# TestProject.net
KiCad netlist of a schematic drawn in Altium Designer
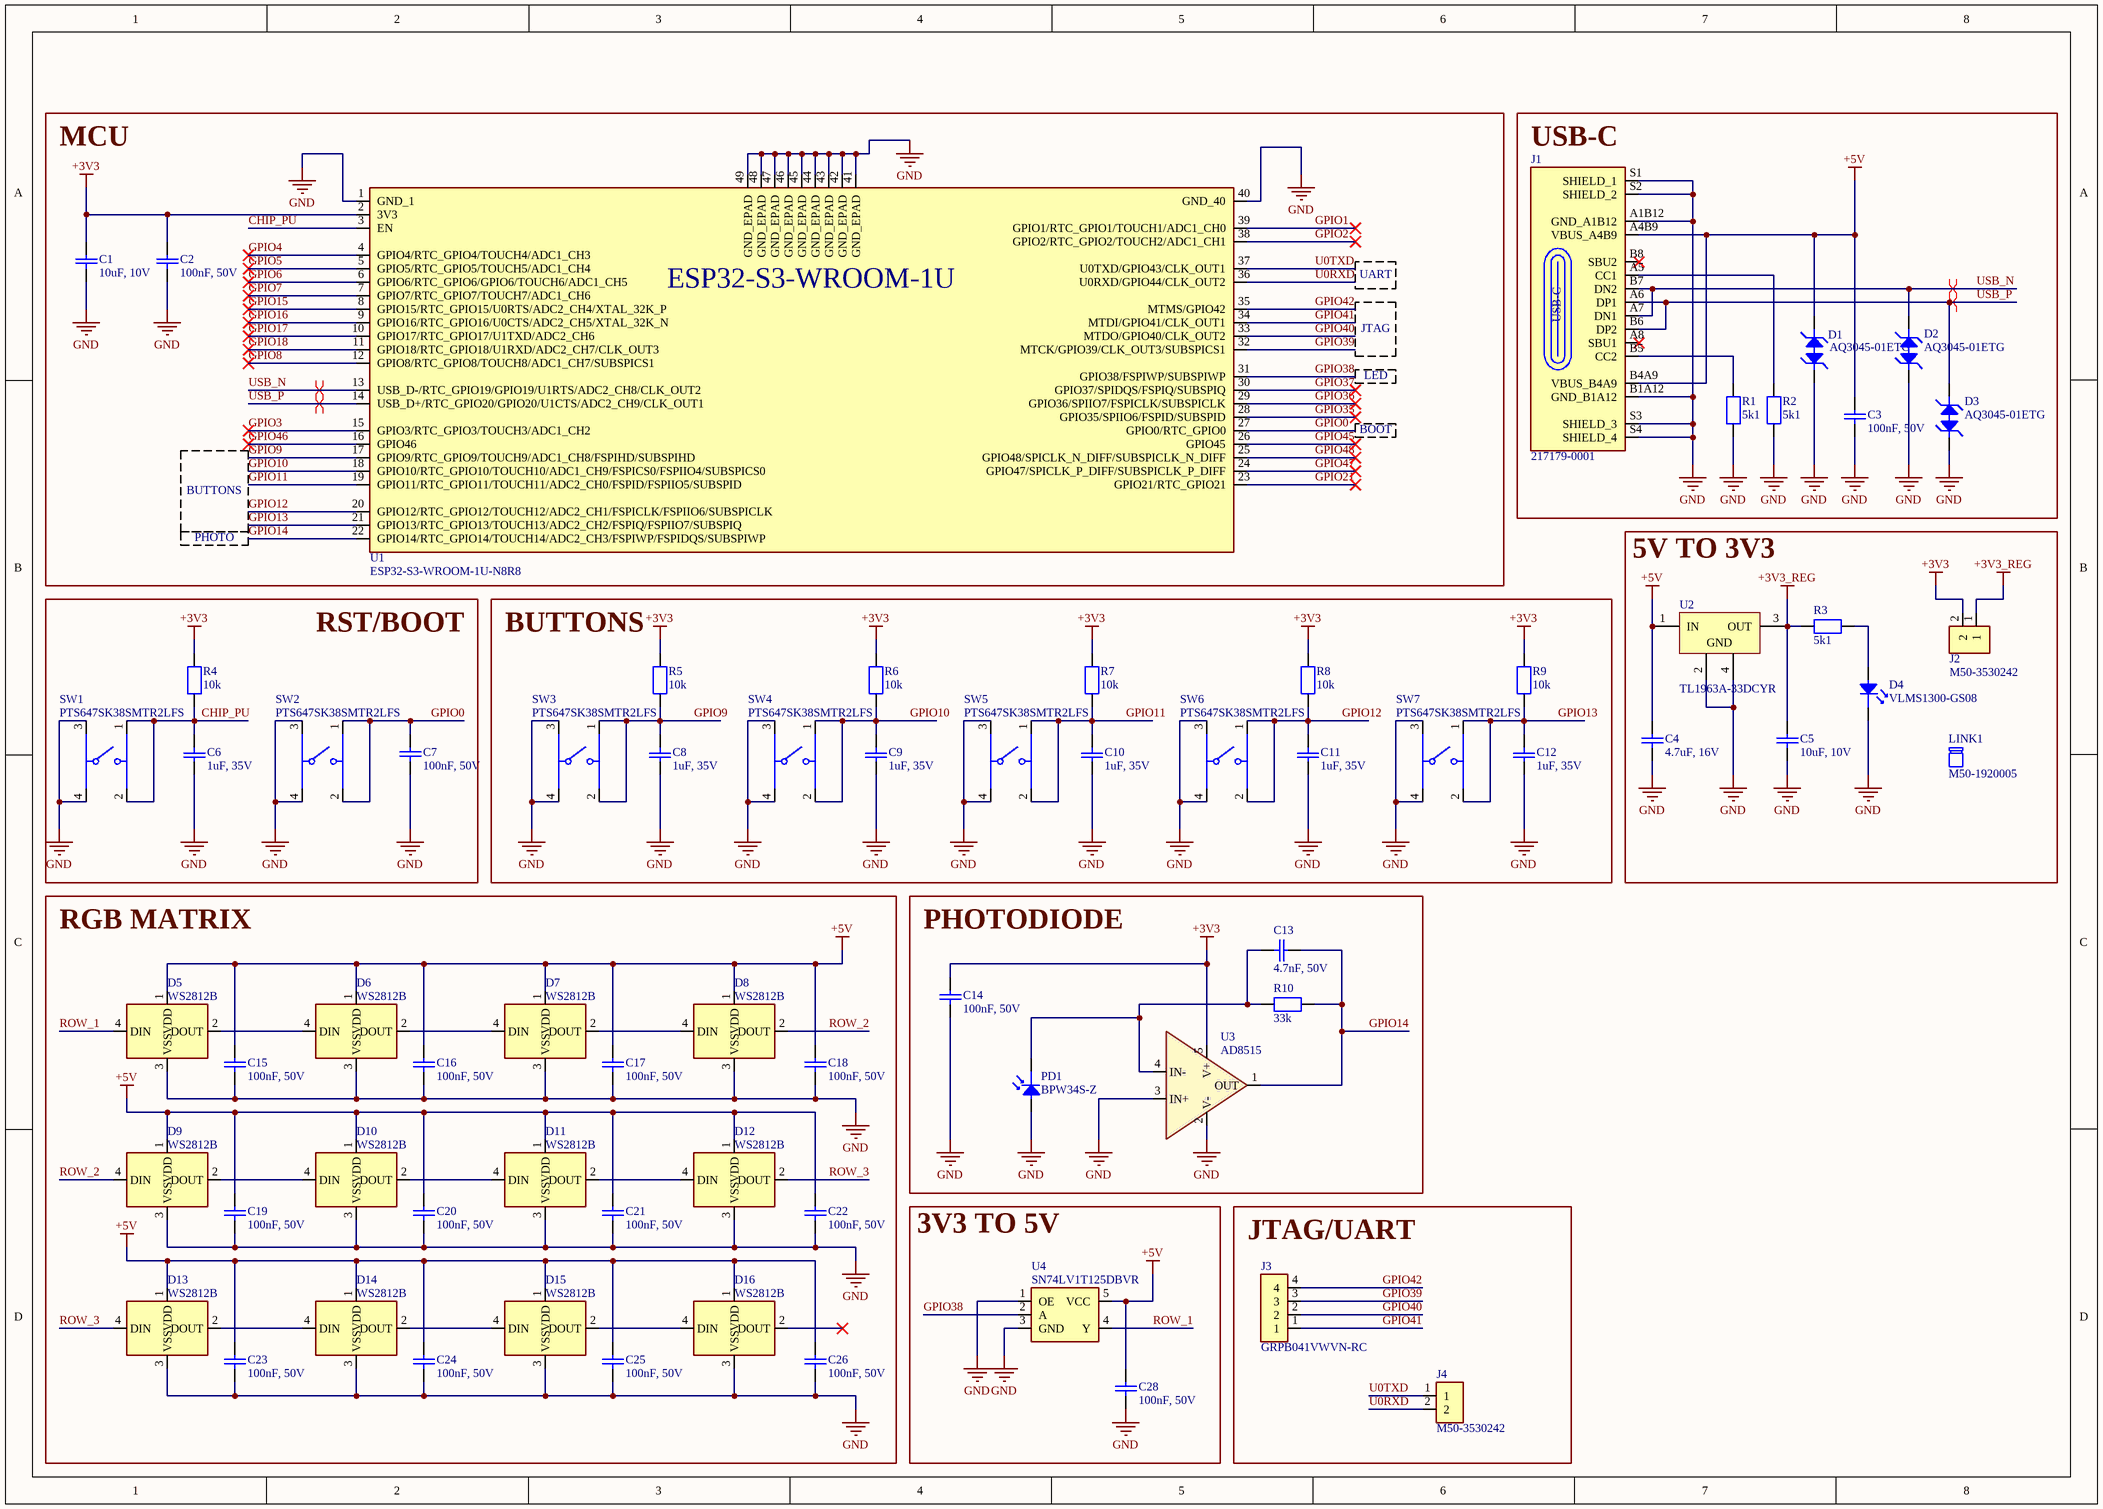
[diagram p0: TestProject.SchDoc]

(export (version "E")
  (design (tool "Eeschema 10.0.6"))
  (components
    (comp (ref "C1")
      (value "10uF, 10V")
      (footprint "CAPC1005X70N")
      (description "CAP CER 10UF 10V X5R 0402")
      (fields
        (field (name "MANUFACTURER") "Samsung")
        (field (name "MANUFACTURER PART NUMBER") "CL05A106MP5NRNC")
      )
      (libsource (lib "Schlib") (part "CL05A106MP5NRNC"))
    )
    (comp (ref "C2")
      (value "100nF, 50V")
      (footprint "CAPC1005X70N")
      (description "CAP CER 0.1UF 50V X7R 0402")
      (fields
        (field (name "MANUFACTURER") "Samsung")
        (field (name "MANUFACTURER PART NUMBER") "CL05B104KB5NNNC")
      )
      (libsource (lib "Schlib") (part "CL05B104KB5NNNC"))
    )
    (comp (ref "C3")
      (value "100nF, 50V")
      (footprint "CAPC1005X70N")
      (description "CAP CER 0.1UF 50V X7R 0402")
      (fields
        (field (name "MANUFACTURER") "Samsung")
        (field (name "MANUFACTURER PART NUMBER") "CL05B104KB5NNNC")
      )
      (libsource (lib "Schlib") (part "CL05B104KB5NNNC"))
    )
    (comp (ref "C4")
      (value "4.7uF, 16V")
      (footprint "CAPC1005X70N")
      (description "CAP CER 4.7UF 16V X5R 0402")
      (fields
        (field (name "MANUFACTURER") "Samsung")
        (field (name "MANUFACTURER PART NUMBER") "CL05A475MO5NUNC")
      )
      (libsource (lib "Schlib") (part "CL05A475MO5NUNC"))
    )
    (comp (ref "C5")
      (value "10uF, 10V")
      (footprint "CAPC1005X70N")
      (description "CAP CER 10UF 10V X5R 0402")
      (fields
        (field (name "MANUFACTURER") "Samsung")
        (field (name "MANUFACTURER PART NUMBER") "CL05A106MP5NRNC")
      )
      (libsource (lib "Schlib") (part "CL05A106MP5NRNC"))
    )
    (comp (ref "C6")
      (value "1uF, 35V")
      (footprint "CAPC1005X70N")
      (description "CAP CER 1UF 35V X5R 0402")
      (fields
        (field (name "MANUFACTURER") "Samsung")
        (field (name "MANUFACTURER PART NUMBER") "CL05A105KL5NRNC")
      )
      (libsource (lib "Schlib") (part "CL05A105KL5NRNC"))
    )
    (comp (ref "C7")
      (value "100nF, 50V")
      (footprint "CAPC1005X70N")
      (description "CAP CER 0.1UF 50V X7R 0402")
      (fields
        (field (name "MANUFACTURER") "Samsung")
        (field (name "MANUFACTURER PART NUMBER") "CL05B104KB5NNNC")
      )
      (libsource (lib "Schlib") (part "CL05B104KB5NNNC"))
    )
    (comp (ref "C8")
      (value "1uF, 35V")
      (footprint "CAPC1005X70N")
      (description "CAP CER 1UF 35V X5R 0402")
      (fields
        (field (name "MANUFACTURER") "Samsung")
        (field (name "MANUFACTURER PART NUMBER") "CL05A105KL5NRNC")
      )
      (libsource (lib "Schlib") (part "CL05A105KL5NRNC"))
    )
    (comp (ref "C9")
      (value "1uF, 35V")
      (footprint "CAPC1005X70N")
      (description "CAP CER 1UF 35V X5R 0402")
      (fields
        (field (name "MANUFACTURER") "Samsung")
        (field (name "MANUFACTURER PART NUMBER") "CL05A105KL5NRNC")
      )
      (libsource (lib "Schlib") (part "CL05A105KL5NRNC"))
    )
    (comp (ref "C10")
      (value "1uF, 35V")
      (footprint "CAPC1005X70N")
      (description "CAP CER 1UF 35V X5R 0402")
      (fields
        (field (name "MANUFACTURER") "Samsung")
        (field (name "MANUFACTURER PART NUMBER") "CL05A105KL5NRNC")
      )
      (libsource (lib "Schlib") (part "CL05A105KL5NRNC"))
    )
    (comp (ref "C11")
      (value "1uF, 35V")
      (footprint "CAPC1005X70N")
      (description "CAP CER 1UF 35V X5R 0402")
      (fields
        (field (name "MANUFACTURER") "Samsung")
        (field (name "MANUFACTURER PART NUMBER") "CL05A105KL5NRNC")
      )
      (libsource (lib "Schlib") (part "CL05A105KL5NRNC"))
    )
    (comp (ref "C12")
      (value "1uF, 35V")
      (footprint "CAPC1005X70N")
      (description "CAP CER 1UF 35V X5R 0402")
      (fields
        (field (name "MANUFACTURER") "Samsung")
        (field (name "MANUFACTURER PART NUMBER") "CL05A105KL5NRNC")
      )
      (libsource (lib "Schlib") (part "CL05A105KL5NRNC"))
    )
    (comp (ref "C13")
      (value "4.7nF, 50V")
      (footprint "CAPC1005X70N")
      (description "CAP CER 4700PF 50V X7R 0402")
      (fields
        (field (name "MANUFACTURER") "Samsung")
        (field (name "MANUFACTURER PART NUMBER") "CL05B472KB5VPNC")
      )
      (libsource (lib "Schlib") (part "CL05B472KB5VPNC"))
    )
    (comp (ref "C14")
      (value "100nF, 50V")
      (footprint "CAPC1005X70N")
      (description "CAP CER 0.1UF 50V X7R 0402")
      (fields
        (field (name "MANUFACTURER") "Samsung")
        (field (name "MANUFACTURER PART NUMBER") "CL05B104KB5NNNC")
      )
      (libsource (lib "Schlib") (part "CL05B104KB5NNNC"))
    )
    (comp (ref "C15")
      (value "100nF, 50V")
      (footprint "CAPC1005X70N")
      (description "CAP CER 0.1UF 50V X7R 0402")
      (fields
        (field (name "MANUFACTURER") "Samsung")
        (field (name "MANUFACTURER PART NUMBER") "CL05B104KB5NNNC")
      )
      (libsource (lib "Schlib") (part "CL05B104KB5NNNC"))
    )
    (comp (ref "C16")
      (value "100nF, 50V")
      (footprint "CAPC1005X70N")
      (description "CAP CER 0.1UF 50V X7R 0402")
      (fields
        (field (name "MANUFACTURER") "Samsung")
        (field (name "MANUFACTURER PART NUMBER") "CL05B104KB5NNNC")
      )
      (libsource (lib "Schlib") (part "CL05B104KB5NNNC"))
    )
    (comp (ref "C17")
      (value "100nF, 50V")
      (footprint "CAPC1005X70N")
      (description "CAP CER 0.1UF 50V X7R 0402")
      (fields
        (field (name "MANUFACTURER") "Samsung")
        (field (name "MANUFACTURER PART NUMBER") "CL05B104KB5NNNC")
      )
      (libsource (lib "Schlib") (part "CL05B104KB5NNNC"))
    )
    (comp (ref "C18")
      (value "100nF, 50V")
      (footprint "CAPC1005X70N")
      (description "CAP CER 0.1UF 50V X7R 0402")
      (fields
        (field (name "MANUFACTURER") "Samsung")
        (field (name "MANUFACTURER PART NUMBER") "CL05B104KB5NNNC")
      )
      (libsource (lib "Schlib") (part "CL05B104KB5NNNC"))
    )
    (comp (ref "C19")
      (value "100nF, 50V")
      (footprint "CAPC1005X70N")
      (description "CAP CER 0.1UF 50V X7R 0402")
      (fields
        (field (name "MANUFACTURER") "Samsung")
        (field (name "MANUFACTURER PART NUMBER") "CL05B104KB5NNNC")
      )
      (libsource (lib "Schlib") (part "CL05B104KB5NNNC"))
    )
    (comp (ref "C20")
      (value "100nF, 50V")
      (footprint "CAPC1005X70N")
      (description "CAP CER 0.1UF 50V X7R 0402")
      (fields
        (field (name "MANUFACTURER") "Samsung")
        (field (name "MANUFACTURER PART NUMBER") "CL05B104KB5NNNC")
      )
      (libsource (lib "Schlib") (part "CL05B104KB5NNNC"))
    )
    (comp (ref "C21")
      (value "100nF, 50V")
      (footprint "CAPC1005X70N")
      (description "CAP CER 0.1UF 50V X7R 0402")
      (fields
        (field (name "MANUFACTURER") "Samsung")
        (field (name "MANUFACTURER PART NUMBER") "CL05B104KB5NNNC")
      )
      (libsource (lib "Schlib") (part "CL05B104KB5NNNC"))
    )
    (comp (ref "C22")
      (value "100nF, 50V")
      (footprint "CAPC1005X70N")
      (description "CAP CER 0.1UF 50V X7R 0402")
      (fields
        (field (name "MANUFACTURER") "Samsung")
        (field (name "MANUFACTURER PART NUMBER") "CL05B104KB5NNNC")
      )
      (libsource (lib "Schlib") (part "CL05B104KB5NNNC"))
    )
    (comp (ref "C23")
      (value "100nF, 50V")
      (footprint "CAPC1005X70N")
      (description "CAP CER 0.1UF 50V X7R 0402")
      (fields
        (field (name "MANUFACTURER") "Samsung")
        (field (name "MANUFACTURER PART NUMBER") "CL05B104KB5NNNC")
      )
      (libsource (lib "Schlib") (part "CL05B104KB5NNNC"))
    )
    (comp (ref "C24")
      (value "100nF, 50V")
      (footprint "CAPC1005X70N")
      (description "CAP CER 0.1UF 50V X7R 0402")
      (fields
        (field (name "MANUFACTURER") "Samsung")
        (field (name "MANUFACTURER PART NUMBER") "CL05B104KB5NNNC")
      )
      (libsource (lib "Schlib") (part "CL05B104KB5NNNC"))
    )
    (comp (ref "C25")
      (value "100nF, 50V")
      (footprint "CAPC1005X70N")
      (description "CAP CER 0.1UF 50V X7R 0402")
      (fields
        (field (name "MANUFACTURER") "Samsung")
        (field (name "MANUFACTURER PART NUMBER") "CL05B104KB5NNNC")
      )
      (libsource (lib "Schlib") (part "CL05B104KB5NNNC"))
    )
    (comp (ref "C26")
      (value "100nF, 50V")
      (footprint "CAPC1005X70N")
      (description "CAP CER 0.1UF 50V X7R 0402")
      (fields
        (field (name "MANUFACTURER") "Samsung")
        (field (name "MANUFACTURER PART NUMBER") "CL05B104KB5NNNC")
      )
      (libsource (lib "Schlib") (part "CL05B104KB5NNNC"))
    )
    (comp (ref "C28")
      (value "100nF, 50V")
      (footprint "CAPC1005X70N")
      (description "CAP CER 0.1UF 50V X7R 0402")
      (fields
        (field (name "MANUFACTURER") "Samsung")
        (field (name "MANUFACTURER PART NUMBER") "CL05B104KB5NNNC")
      )
      (libsource (lib "Schlib") (part "CL05B104KB5NNNC"))
    )
    (comp (ref "D1")
      (value "AQ3045-01ETG")
      (footprint "RTVS_SOD882_LTF")
      (description "TVS DIODE 5.3VWM 12VC SOD882")
      (fields (field (name "MANUFACTURER") "Littelfuse") (field (name "LCSC PART NUMBER") "C3710326"))
      (libsource (lib "Schlib") (part "AQ3045-01ETG"))
    )
    (comp (ref "D2")
      (value "AQ3045-01ETG")
      (footprint "RTVS_SOD882_LTF")
      (description "TVS DIODE 5.3VWM 12VC SOD882")
      (fields (field (name "MANUFACTURER") "Littelfuse") (field (name "LCSC PART NUMBER") "C3710326"))
      (libsource (lib "Schlib") (part "AQ3045-01ETG"))
    )
    (comp (ref "D3")
      (value "AQ3045-01ETG")
      (footprint "RTVS_SOD882_LTF")
      (description "TVS DIODE 5.3VWM 12VC SOD882")
      (fields (field (name "MANUFACTURER") "Littelfuse") (field (name "LCSC PART NUMBER") "C3710326"))
      (libsource (lib "Schlib") (part "AQ3045-01ETG"))
    )
    (comp (ref "D4")
      (value "VLMS1300-GS08")
      (footprint "LED_VISHAY_VLMX1300_VIS")
      (description "LED RED 0603 SMD")
      (fields
        (field (name "MANUFACTURER") "Vishay Semiconductors")
        (field (name "LCSC PART NUMBER") "C83242")
      )
      (libsource (lib "Schlib") (part "VLMS1300-GS08"))
    )
    (comp (ref "D5")
      (value "WS2812B")
      (footprint "COM-16347_SPK")
      (description "ADDRESS LED RED/GRN/BLUE")
      (fields (field (name "MANUFACTURER") "SparkFun") (field (name "MANUFACTURER PART NUMBER") "16347"))
      (libsource (lib "Schlib") (part "16347"))
    )
    (comp (ref "D6")
      (value "WS2812B")
      (footprint "COM-16347_SPK")
      (description "ADDRESS LED RED/GRN/BLUE")
      (fields (field (name "MANUFACTURER") "SparkFun") (field (name "MANUFACTURER PART NUMBER") "16347"))
      (libsource (lib "Schlib") (part "16347"))
    )
    (comp (ref "D7")
      (value "WS2812B")
      (footprint "COM-16347_SPK")
      (description "ADDRESS LED RED/GRN/BLUE")
      (fields (field (name "MANUFACTURER") "SparkFun") (field (name "MANUFACTURER PART NUMBER") "16347"))
      (libsource (lib "Schlib") (part "16347"))
    )
    (comp (ref "D8")
      (value "WS2812B")
      (footprint "COM-16347_SPK")
      (description "ADDRESS LED RED/GRN/BLUE")
      (fields (field (name "MANUFACTURER") "SparkFun") (field (name "MANUFACTURER PART NUMBER") "16347"))
      (libsource (lib "Schlib") (part "16347"))
    )
    (comp (ref "D9")
      (value "WS2812B")
      (footprint "COM-16347_SPK")
      (description "ADDRESS LED RED/GRN/BLUE")
      (fields (field (name "MANUFACTURER") "SparkFun") (field (name "MANUFACTURER PART NUMBER") "16347"))
      (libsource (lib "Schlib") (part "16347"))
    )
    (comp (ref "D10")
      (value "WS2812B")
      (footprint "COM-16347_SPK")
      (description "ADDRESS LED RED/GRN/BLUE")
      (fields (field (name "MANUFACTURER") "SparkFun") (field (name "MANUFACTURER PART NUMBER") "16347"))
      (libsource (lib "Schlib") (part "16347"))
    )
    (comp (ref "D11")
      (value "WS2812B")
      (footprint "COM-16347_SPK")
      (description "ADDRESS LED RED/GRN/BLUE")
      (fields (field (name "MANUFACTURER") "SparkFun") (field (name "MANUFACTURER PART NUMBER") "16347"))
      (libsource (lib "Schlib") (part "16347"))
    )
    (comp (ref "D12")
      (value "WS2812B")
      (footprint "COM-16347_SPK")
      (description "ADDRESS LED RED/GRN/BLUE")
      (fields (field (name "MANUFACTURER") "SparkFun") (field (name "MANUFACTURER PART NUMBER") "16347"))
      (libsource (lib "Schlib") (part "16347"))
    )
    (comp (ref "D13")
      (value "WS2812B")
      (footprint "COM-16347_SPK")
      (description "ADDRESS LED RED/GRN/BLUE")
      (fields (field (name "MANUFACTURER") "SparkFun") (field (name "MANUFACTURER PART NUMBER") "16347"))
      (libsource (lib "Schlib") (part "16347"))
    )
    (comp (ref "D14")
      (value "WS2812B")
      (footprint "COM-16347_SPK")
      (description "ADDRESS LED RED/GRN/BLUE")
      (fields (field (name "MANUFACTURER") "SparkFun") (field (name "MANUFACTURER PART NUMBER") "16347"))
      (libsource (lib "Schlib") (part "16347"))
    )
    (comp (ref "D15")
      (value "WS2812B")
      (footprint "COM-16347_SPK")
      (description "ADDRESS LED RED/GRN/BLUE")
      (fields (field (name "MANUFACTURER") "SparkFun") (field (name "MANUFACTURER PART NUMBER") "16347"))
      (libsource (lib "Schlib") (part "16347"))
    )
    (comp (ref "D16")
      (value "WS2812B")
      (footprint "COM-16347_SPK")
      (description "ADDRESS LED RED/GRN/BLUE")
      (fields (field (name "MANUFACTURER") "SparkFun") (field (name "MANUFACTURER PART NUMBER") "16347"))
      (libsource (lib "Schlib") (part "16347"))
    )
    (comp (ref "J1")
      (value "217179-0001")
      (footprint "FP-2171790001-MFG")
      (description "CONN RCP USB2.0 TYP C 24P SMD RA")
      (fields (field (name "MANUFACTURER") "Molex") (field (name "LCSC PART NUMBER") "C3197684"))
      (libsource (lib "Schlib") (part "217179-0001"))
    )
    (comp (ref "J2")
      (value "M50-3530242")
      (footprint "HARWIN_M50-3530242")
      (description "CONN HEADER VERT 2POS 1.27MM")
      (fields (field (name "MANUFACTURER") "Harwin") (field (name "LCSC PART NUMBER") "C3325334"))
      (libsource (lib "") (part "M50-3530242_1"))
    )
    (comp (ref "J3")
      (value "GRPB041VWVN-RC")
      (footprint "GRPB041VWVN-RC")
      (description "CONN HEADER VERT 4POS 1.27MM")
      (fields (field (name "MANUFACTURER") "Sullins") (field (name "LCSC PART NUMBER") "C7198233"))
      (libsource (lib "Schlib") (part "GRPB041VWVN-RC"))
    )
    (comp (ref "J4")
      (value "M50-3530242")
      (footprint "HARWIN_M50-3530242")
      (description "CONN HEADER VERT 2POS 1.27MM")
      (fields (field (name "MANUFACTURER") "Harwin") (field (name "LCSC PART NUMBER") "C3325334"))
      (libsource (lib "Schlib") (part "M50-3530242"))
    )
    (comp (ref "LINK1")
      (value "M50-1920005")
      (description "CONN SHUNT 1.27MM RED")
      (fields (field (name "MANUFACTURER") "Harwin") (field (name "LCSC PART NUMBER") "C6985646"))
      (libsource (lib "Schlib") (part "M50-1920005"))
    )
    (comp (ref "PD1")
      (value "BPW34S-Z")
      (footprint "DIO_BPW_34_S-Z")
      (description "SENSOR PHOTODIODE 850NM 2SMD GW")
      (fields (field (name "MANUFACTURER") "Osram Opto") (field (name "LCSC PART NUMBER") "C67891"))
      (libsource (lib "Schlib") (part "BPW34S-Z"))
    )
    (comp (ref "R1")
      (value "5k1")
      (footprint "RESC1005X37N")
      (description "RES SMD 5.1K OHM 1% 1/16W 0402")
      (fields
        (field (name "MANUFACTURER") "Yageo")
        (field (name "MANUFACTURER PART NUMBER") "AC0402FR-075K1L")
      )
      (libsource (lib "Schlib") (part "AC0402FR-075K1L"))
    )
    (comp (ref "R2")
      (value "5k1")
      (footprint "RESC1005X37N")
      (description "RES SMD 5.1K OHM 1% 1/16W 0402")
      (fields
        (field (name "MANUFACTURER") "Yageo")
        (field (name "MANUFACTURER PART NUMBER") "AC0402FR-075K1L")
      )
      (libsource (lib "Schlib") (part "AC0402FR-075K1L"))
    )
    (comp (ref "R3")
      (value "5k1")
      (footprint "RESC1005X37N")
      (description "RES SMD 5.1K OHM 1% 1/16W 0402")
      (fields
        (field (name "MANUFACTURER") "Yageo")
        (field (name "MANUFACTURER PART NUMBER") "AC0402FR-075K1L")
      )
      (libsource (lib "Schlib") (part "AC0402FR-075K1L"))
    )
    (comp (ref "R4")
      (value "10k")
      (footprint "RESC1005X37N")
      (description "RES SMD 10K OHM 1% 1/16W 0402")
      (fields
        (field (name "MANUFACTURER") "Yageo")
        (field (name "MANUFACTURER PART NUMBER") "AC0402FR-0710KL")
      )
      (libsource (lib "Schlib") (part "AC0402FR-0710KL"))
    )
    (comp (ref "R5")
      (value "10k")
      (footprint "RESC1005X37N")
      (description "RES SMD 10K OHM 1% 1/16W 0402")
      (fields
        (field (name "MANUFACTURER") "Yageo")
        (field (name "MANUFACTURER PART NUMBER") "AC0402FR-0710KL")
      )
      (libsource (lib "Schlib") (part "AC0402FR-0710KL"))
    )
    (comp (ref "R6")
      (value "10k")
      (footprint "RESC1005X37N")
      (description "RES SMD 10K OHM 1% 1/16W 0402")
      (fields
        (field (name "MANUFACTURER") "Yageo")
        (field (name "MANUFACTURER PART NUMBER") "AC0402FR-0710KL")
      )
      (libsource (lib "Schlib") (part "AC0402FR-0710KL"))
    )
    (comp (ref "R7")
      (value "10k")
      (footprint "RESC1005X37N")
      (description "RES SMD 10K OHM 1% 1/16W 0402")
      (fields
        (field (name "MANUFACTURER") "Yageo")
        (field (name "MANUFACTURER PART NUMBER") "AC0402FR-0710KL")
      )
      (libsource (lib "Schlib") (part "AC0402FR-0710KL"))
    )
    (comp (ref "R8")
      (value "10k")
      (footprint "RESC1005X37N")
      (description "RES SMD 10K OHM 1% 1/16W 0402")
      (fields
        (field (name "MANUFACTURER") "Yageo")
        (field (name "MANUFACTURER PART NUMBER") "AC0402FR-0710KL")
      )
      (libsource (lib "Schlib") (part "AC0402FR-0710KL"))
    )
    (comp (ref "R9")
      (value "10k")
      (footprint "RESC1005X37N")
      (description "RES SMD 10K OHM 1% 1/16W 0402")
      (fields
        (field (name "MANUFACTURER") "Yageo")
        (field (name "MANUFACTURER PART NUMBER") "AC0402FR-0710KL")
      )
      (libsource (lib "Schlib") (part "AC0402FR-0710KL"))
    )
    (comp (ref "R10")
      (value "33k")
      (footprint "RESC1005X37N")
      (description "RES SMD 33K OHM 1% 1/16W 0402")
      (fields
        (field (name "MANUFACTURER") "Yageo")
        (field (name "MANUFACTURER PART NUMBER") "AC0402FR-0733KL")
      )
      (libsource (lib "Schlib") (part "AC0402FR-0733KL"))
    )
    (comp (ref "SW1")
      (value "PTS647SK38SMTR2LFS")
      (footprint "FP-PTS647SK38SMTR2LFS-MFG")
      (description "SWITCH TACTILE SPST-NO 0.05A 12V")
      (fields (field (name "MANUFACTURER") "ITT C&K") (field (name "LCSC PART NUMBER") "C2798978"))
      (libsource (lib "Schlib") (part "PTS647SK38SMTR2LFS"))
    )
    (comp (ref "SW2")
      (value "PTS647SK38SMTR2LFS")
      (footprint "FP-PTS647SK38SMTR2LFS-MFG")
      (description "SWITCH TACTILE SPST-NO 0.05A 12V")
      (fields (field (name "MANUFACTURER") "ITT C&K") (field (name "LCSC PART NUMBER") "C2798978"))
      (libsource (lib "Schlib") (part "PTS647SK38SMTR2LFS"))
    )
    (comp (ref "SW3")
      (value "PTS647SK38SMTR2LFS")
      (footprint "FP-PTS647SK38SMTR2LFS-MFG")
      (description "SWITCH TACTILE SPST-NO 0.05A 12V")
      (fields (field (name "MANUFACTURER") "ITT C&K") (field (name "LCSC PART NUMBER") "C2798978"))
      (libsource (lib "Schlib") (part "PTS647SK38SMTR2LFS"))
    )
    (comp (ref "SW4")
      (value "PTS647SK38SMTR2LFS")
      (footprint "FP-PTS647SK38SMTR2LFS-MFG")
      (description "SWITCH TACTILE SPST-NO 0.05A 12V")
      (fields (field (name "MANUFACTURER") "ITT C&K") (field (name "LCSC PART NUMBER") "C2798978"))
      (libsource (lib "Schlib") (part "PTS647SK38SMTR2LFS"))
    )
    (comp (ref "SW5")
      (value "PTS647SK38SMTR2LFS")
      (footprint "FP-PTS647SK38SMTR2LFS-MFG")
      (description "SWITCH TACTILE SPST-NO 0.05A 12V")
      (fields (field (name "MANUFACTURER") "ITT C&K") (field (name "LCSC PART NUMBER") "C2798978"))
      (libsource (lib "Schlib") (part "PTS647SK38SMTR2LFS"))
    )
    (comp (ref "SW6")
      (value "PTS647SK38SMTR2LFS")
      (footprint "FP-PTS647SK38SMTR2LFS-MFG")
      (description "SWITCH TACTILE SPST-NO 0.05A 12V")
      (fields (field (name "MANUFACTURER") "ITT C&K") (field (name "LCSC PART NUMBER") "C2798978"))
      (libsource (lib "Schlib") (part "PTS647SK38SMTR2LFS"))
    )
    (comp (ref "SW7")
      (value "PTS647SK38SMTR2LFS")
      (footprint "FP-PTS647SK38SMTR2LFS-MFG")
      (description "SWITCH TACTILE SPST-NO 0.05A 12V")
      (fields (field (name "MANUFACTURER") "ITT C&K") (field (name "LCSC PART NUMBER") "C2798978"))
      (libsource (lib "Schlib") (part "PTS647SK38SMTR2LFS"))
    )
    (comp (ref "U1")
      (value "ESP32-S3-WROOM-1U-N8R8")
      (footprint "XCVR_ESP32-S3-WROOM-1U")
      (description "SMD Module, ESP32-S3R8 With 8 mb")
      (fields (field (name "MANUFACTURER") "Espressif Systems") (field (name "LCSC PART NUMBER") "C2980300"))
      (libsource (lib "Schlib") (part "ESP32-S3-WROOM-1U-N8R8"))
    )
    (comp (ref "U2")
      (value "TL1963A-33DCYR")
      (footprint "DCY0004A_N")
      (description "IC REG LIN 3.3V 1.5A SOT-223-4")
      (fields (field (name "MANUFACTURER") "Texas Instruments") (field (name "LCSC PART NUMBER") "C181262"))
      (libsource (lib "Schlib") (part "TL1963A-33DCYR"))
    )
    (comp (ref "U3")
      (value "AD8515")
      (footprint "SOT95P280X145-5N")
      (description "IC OPAMP GP 1 CIRCUIT SOT23-5")
      (fields
        (field (name "MANUFACTURER") "Analog Devices")
        (field (name "MANUFACTURER PART NUMBER") "AD8515ARTZ-REEL7")
      )
      (libsource (lib "Schlib") (part "AD8515ARTZ-REEL7"))
    )
    (comp (ref "U4")
      (value "SN74LV1T125DBVR")
      (footprint "SOT95P280X145-5N")
      (description "IC BUFF NON-INVERT 5.5V SOT-23-5")
      (fields (field (name "MANUFACTURER") "Texas Instruments") (field (name "LCSC PART NUMBER") "C473338"))
      (libsource (lib "Schlib") (part "SN74LV1T125DBVR"))
    )
  )
  (nets
    (net (code "1") (name "+3V3") (class "Default")
      (node (ref "C1") (pin "2") (pinfunction "2_2") (pintype "passive"))
      (node (ref "C14") (pin "2") (pinfunction "2_2") (pintype "passive"))
      (node (ref "C2") (pin "2") (pinfunction "2_2") (pintype "passive"))
      (node (ref "J2") (pin "2") (pinfunction "2_2") (pintype "passive"))
      (node (ref "R4") (pin "2") (pinfunction "2_2") (pintype "passive"))
      (node (ref "R5") (pin "2") (pinfunction "2_2") (pintype "passive"))
      (node (ref "R6") (pin "2") (pinfunction "2_2") (pintype "passive"))
      (node (ref "R7") (pin "2") (pinfunction "2_2") (pintype "passive"))
      (node (ref "R8") (pin "2") (pinfunction "2_2") (pintype "passive"))
      (node (ref "R9") (pin "2") (pinfunction "2_2") (pintype "passive"))
      (node (ref "U1") (pin "2") (pinfunction "3V3_2") (pintype "passive"))
      (node (ref "U3") (pin "5") (pinfunction "V+_5") (pintype "passive"))
    )
    (net (code "2") (name "+3V3_REG") (class "Default")
      (node (ref "C5") (pin "2") (pinfunction "2_2") (pintype "passive"))
      (node (ref "J2") (pin "1") (pinfunction "1_1") (pintype "passive"))
      (node (ref "R3") (pin "2") (pinfunction "2_2") (pintype "passive"))
      (node (ref "U2") (pin "3") (pinfunction "OUT_3") (pintype "power_in"))
    )
    (net (code "3") (name "+5V") (class "Default")
      (node (ref "C15") (pin "2") (pinfunction "2_2") (pintype "passive"))
      (node (ref "C16") (pin "2") (pinfunction "2_2") (pintype "passive"))
      (node (ref "C17") (pin "2") (pinfunction "2_2") (pintype "passive"))
      (node (ref "C18") (pin "2") (pinfunction "2_2") (pintype "passive"))
      (node (ref "C19") (pin "2") (pinfunction "2_2") (pintype "passive"))
      (node (ref "C20") (pin "2") (pinfunction "2_2") (pintype "passive"))
      (node (ref "C21") (pin "2") (pinfunction "2_2") (pintype "passive"))
      (node (ref "C22") (pin "2") (pinfunction "2_2") (pintype "passive"))
      (node (ref "C23") (pin "2") (pinfunction "2_2") (pintype "passive"))
      (node (ref "C24") (pin "2") (pinfunction "2_2") (pintype "passive"))
      (node (ref "C25") (pin "2") (pinfunction "2_2") (pintype "passive"))
      (node (ref "C26") (pin "2") (pinfunction "2_2") (pintype "passive"))
      (node (ref "C28") (pin "2") (pinfunction "2_2") (pintype "passive"))
      (node (ref "C3") (pin "2") (pinfunction "2_2") (pintype "passive"))
      (node (ref "C4") (pin "2") (pinfunction "2_2") (pintype "passive"))
      (node (ref "D1") (pin "2") (pinfunction "2_2") (pintype "passive"))
      (node (ref "D10") (pin "1") (pinfunction "VDD_1") (pintype "passive"))
      (node (ref "D11") (pin "1") (pinfunction "VDD_1") (pintype "passive"))
      (node (ref "D12") (pin "1") (pinfunction "VDD_1") (pintype "passive"))
      (node (ref "D13") (pin "1") (pinfunction "VDD_1") (pintype "passive"))
      (node (ref "D14") (pin "1") (pinfunction "VDD_1") (pintype "passive"))
      (node (ref "D15") (pin "1") (pinfunction "VDD_1") (pintype "passive"))
      (node (ref "D16") (pin "1") (pinfunction "VDD_1") (pintype "passive"))
      (node (ref "D5") (pin "1") (pinfunction "VDD_1") (pintype "passive"))
      (node (ref "D6") (pin "1") (pinfunction "VDD_1") (pintype "passive"))
      (node (ref "D7") (pin "1") (pinfunction "VDD_1") (pintype "passive"))
      (node (ref "D8") (pin "1") (pinfunction "VDD_1") (pintype "passive"))
      (node (ref "D9") (pin "1") (pinfunction "VDD_1") (pintype "passive"))
      (node (ref "J1") (pin "A4B9") (pinfunction "VBUS_A4B9_A4B9") (pintype "passive"))
      (node (ref "J1") (pin "B4A9") (pinfunction "VBUS_B4A9_B4A9") (pintype "passive"))
      (node (ref "U2") (pin "1") (pinfunction "IN_1") (pintype "power_in"))
      (node (ref "U4") (pin "5") (pinfunction "VCC_5") (pintype "passive"))
    )
    (net (code "4") (name "/CHIP_PU") (class "Default")
      (node (ref "C6") (pin "1") (pinfunction "1_1") (pintype "passive"))
      (node (ref "R4") (pin "1") (pinfunction "1_1") (pintype "passive"))
      (node (ref "SW1") (pin "1") (pinfunction "1_1") (pintype "passive"))
      (node (ref "SW1") (pin "2") (pinfunction "2_2") (pintype "passive"))
      (node (ref "U1") (pin "3") (pinfunction "EN_3") (pintype "passive"))
    )
    (net (code "5") (name "/GPIO0") (class "Default")
      (node (ref "C7") (pin "2") (pinfunction "2_2") (pintype "passive"))
      (node (ref "SW2") (pin "1") (pinfunction "1_1") (pintype "passive"))
      (node (ref "SW2") (pin "2") (pinfunction "2_2") (pintype "passive"))
      (node (ref "U1") (pin "27") (pinfunction "GPIO0/RTC_GPIO0_27") (pintype "passive"))
    )
    (net (code "6") (name "/GPIO1") (class "Default")
      (node (ref "U1") (pin "39") (pinfunction "GPIO1/RTC_GPIO1/TOUCH1/ADC1_CH0_39") (pintype "passive+no_connect"))
    )
    (net (code "7") (name "/GPIO2") (class "Default")
      (node (ref "U1") (pin "38") (pinfunction "GPIO2/RTC_GPIO2/TOUCH2/ADC1_CH1_38") (pintype "passive+no_connect"))
    )
    (net (code "8") (name "/GPIO3") (class "Default")
      (node (ref "U1") (pin "15") (pinfunction "GPIO3/RTC_GPIO3/TOUCH3/ADC1_CH2_15") (pintype "passive+no_connect"))
    )
    (net (code "9") (name "/GPIO4") (class "Default")
      (node (ref "U1") (pin "4") (pinfunction "GPIO4/RTC_GPIO4/TOUCH4/ADC1_CH3_4") (pintype "passive+no_connect"))
    )
    (net (code "10") (name "/GPIO5") (class "Default")
      (node (ref "U1") (pin "5") (pinfunction "GPIO5/RTC_GPIO5/TOUCH5/ADC1_CH4_5") (pintype "passive+no_connect"))
    )
    (net (code "11") (name "/GPIO6") (class "Default")
      (node (ref "U1") (pin "6") (pinfunction "GPIO6/RTC_GPIO6/GPIO6/TOUCH6/ADC1_CH5_6") (pintype "passive+no_connect"))
    )
    (net (code "12") (name "/GPIO7") (class "Default")
      (node (ref "U1") (pin "7") (pinfunction "GPIO7/RTC_GPIO7/TOUCH7/ADC1_CH6_7") (pintype "passive+no_connect"))
    )
    (net (code "13") (name "/GPIO8") (class "Default")
      (node (ref "U1") (pin "12") (pinfunction "GPIO8/RTC_GPIO8/TOUCH8/ADC1_CH7/SUBSPICS1_12") (pintype "passive+no_connect"))
    )
    (net (code "14") (name "/GPIO9") (class "Default")
      (node (ref "C8") (pin "1") (pinfunction "1_1") (pintype "passive"))
      (node (ref "R5") (pin "1") (pinfunction "1_1") (pintype "passive"))
      (node (ref "SW3") (pin "1") (pinfunction "1_1") (pintype "passive"))
      (node (ref "SW3") (pin "2") (pinfunction "2_2") (pintype "passive"))
      (node (ref "U1") (pin "17") (pinfunction "GPIO9/RTC_GPIO9/TOUCH9/ADC1_CH8/FSPIHD/SUBSPIHD_17") (pintype "passive"))
    )
    (net (code "15") (name "/GPIO10") (class "Default")
      (node (ref "C9") (pin "1") (pinfunction "1_1") (pintype "passive"))
      (node (ref "R6") (pin "1") (pinfunction "1_1") (pintype "passive"))
      (node (ref "SW4") (pin "1") (pinfunction "1_1") (pintype "passive"))
      (node (ref "SW4") (pin "2") (pinfunction "2_2") (pintype "passive"))
      (node (ref "U1") (pin "18") (pinfunction "GPIO10/RTC_GPIO10/TOUCH10/ADC1_CH9/FSPICS0/FSPIIO4/SUBSPICS0_18") (pintype "passive"))
    )
    (net (code "16") (name "/GPIO11") (class "Default")
      (node (ref "C10") (pin "1") (pinfunction "1_1") (pintype "passive"))
      (node (ref "R7") (pin "1") (pinfunction "1_1") (pintype "passive"))
      (node (ref "SW5") (pin "1") (pinfunction "1_1") (pintype "passive"))
      (node (ref "SW5") (pin "2") (pinfunction "2_2") (pintype "passive"))
      (node (ref "U1") (pin "19") (pinfunction "GPIO11/RTC_GPIO11/TOUCH11/ADC2_CH0/FSPID/FSPIIO5/SUBSPID_19") (pintype "passive"))
    )
    (net (code "17") (name "/GPIO12") (class "Default")
      (node (ref "C11") (pin "1") (pinfunction "1_1") (pintype "passive"))
      (node (ref "R8") (pin "1") (pinfunction "1_1") (pintype "passive"))
      (node (ref "SW6") (pin "1") (pinfunction "1_1") (pintype "passive"))
      (node (ref "SW6") (pin "2") (pinfunction "2_2") (pintype "passive"))
      (node (ref "U1") (pin "20") (pinfunction "GPIO12/RTC_GPIO12/TOUCH12/ADC2_CH1/FSPICLK/FSPIIO6/SUBSPICLK_20") (pintype "passive"))
    )
    (net (code "18") (name "/GPIO13") (class "Default")
      (node (ref "C12") (pin "1") (pinfunction "1_1") (pintype "passive"))
      (node (ref "R9") (pin "1") (pinfunction "1_1") (pintype "passive"))
      (node (ref "SW7") (pin "1") (pinfunction "1_1") (pintype "passive"))
      (node (ref "SW7") (pin "2") (pinfunction "2_2") (pintype "passive"))
      (node (ref "U1") (pin "21") (pinfunction "GPIO13/RTC_GPIO13/TOUCH13/ADC2_CH2/FSPIQ/FSPIIO7/SUBSPIQ_21") (pintype "passive"))
    )
    (net (code "19") (name "/GPIO14") (class "Default")
      (node (ref "C13") (pin "2") (pinfunction "2_2") (pintype "passive"))
      (node (ref "R10") (pin "2") (pinfunction "2_2") (pintype "passive"))
      (node (ref "U1") (pin "22") (pinfunction "GPIO14/RTC_GPIO14/TOUCH14/ADC2_CH3/FSPIWP/FSPIDQS/SUBSPIWP_22") (pintype "passive"))
      (node (ref "U3") (pin "1") (pinfunction "OUT_1") (pintype "passive"))
    )
    (net (code "20") (name "/GPIO15") (class "Default")
      (node (ref "U1") (pin "8") (pinfunction "GPIO15/RTC_GPIO15/U0RTS/ADC2_CH4/XTAL_32K_P_8") (pintype "passive+no_connect"))
    )
    (net (code "21") (name "/GPIO16") (class "Default")
      (node (ref "U1") (pin "9") (pinfunction "GPIO16/RTC_GPIO16/U0CTS/ADC2_CH5/XTAL_32K_N_9") (pintype "passive+no_connect"))
    )
    (net (code "22") (name "/GPIO17") (class "Default")
      (node (ref "U1") (pin "10") (pinfunction "GPIO17/RTC_GPIO17/U1TXD/ADC2_CH6_10") (pintype "passive+no_connect"))
    )
    (net (code "23") (name "/GPIO18") (class "Default")
      (node (ref "U1") (pin "11") (pinfunction "GPIO18/RTC_GPIO18/U1RXD/ADC2_CH7/CLK_OUT3_11") (pintype "passive+no_connect"))
    )
    (net (code "24") (name "/GPIO21") (class "Default")
      (node (ref "U1") (pin "23") (pinfunction "GPIO21/RTC_GPIO21_23") (pintype "passive+no_connect"))
    )
    (net (code "25") (name "/GPIO35") (class "Default")
      (node (ref "U1") (pin "28") (pinfunction "GPIO35/SPIIO6/FSPID/SUBSPID_28") (pintype "passive+no_connect"))
    )
    (net (code "26") (name "/GPIO36") (class "Default")
      (node (ref "U1") (pin "29") (pinfunction "GPIO36/SPIIO7/FSPICLK/SUBSPICLK_29") (pintype "passive+no_connect"))
    )
    (net (code "27") (name "/GPIO37") (class "Default")
      (node (ref "U1") (pin "30") (pinfunction "GPIO37/SPIDQS/FSPIQ/SUBSPIQ_30") (pintype "passive+no_connect"))
    )
    (net (code "28") (name "/GPIO38") (class "Default")
      (node (ref "U1") (pin "31") (pinfunction "GPIO38/FSPIWP/SUBSPIWP_31") (pintype "passive"))
      (node (ref "U4") (pin "2") (pinfunction "A_2") (pintype "passive"))
    )
    (net (code "29") (name "/GPIO39") (class "Default")
      (node (ref "J3") (pin "3") (pinfunction "3_3") (pintype "passive"))
      (node (ref "U1") (pin "32") (pinfunction "MTCK/GPIO39/CLK_OUT3/SUBSPICS1_32") (pintype "passive"))
    )
    (net (code "30") (name "/GPIO40") (class "Default")
      (node (ref "J3") (pin "2") (pinfunction "2_2") (pintype "passive"))
      (node (ref "U1") (pin "33") (pinfunction "MTDO/GPIO40/CLK_OUT2_33") (pintype "passive"))
    )
    (net (code "31") (name "/GPIO41") (class "Default")
      (node (ref "J3") (pin "1") (pinfunction "1_1") (pintype "passive"))
      (node (ref "U1") (pin "34") (pinfunction "MTDI/GPIO41/CLK_OUT1_34") (pintype "passive"))
    )
    (net (code "32") (name "/GPIO42") (class "Default")
      (node (ref "J3") (pin "4") (pinfunction "4_4") (pintype "passive"))
      (node (ref "U1") (pin "35") (pinfunction "MTMS/GPIO42_35") (pintype "passive"))
    )
    (net (code "33") (name "/GPIO45") (class "Default")
      (node (ref "U1") (pin "26") (pinfunction "GPIO45_26") (pintype "passive+no_connect"))
    )
    (net (code "34") (name "/GPIO46") (class "Default")
      (node (ref "U1") (pin "16") (pinfunction "GPIO46_16") (pintype "passive+no_connect"))
    )
    (net (code "35") (name "/GPIO47") (class "Default")
      (node (ref "U1") (pin "24") (pinfunction "GPIO47/SPICLK_P_DIFF/SUBSPICLK_P_DIFF_24") (pintype "passive+no_connect"))
    )
    (net (code "36") (name "/GPIO48") (class "Default")
      (node (ref "U1") (pin "25") (pinfunction "GPIO48/SPICLK_N_DIFF/SUBSPICLK_N_DIFF_25") (pintype "passive+no_connect"))
    )
    (net (code "37") (name "/ROW_1") (class "Default")
      (node (ref "D5") (pin "4") (pinfunction "DIN_4") (pintype "passive"))
      (node (ref "U4") (pin "4") (pinfunction "Y_4") (pintype "passive"))
    )
    (net (code "38") (name "/ROW_2") (class "Default")
      (node (ref "D8") (pin "2") (pinfunction "DOUT_2") (pintype "passive"))
      (node (ref "D9") (pin "4") (pinfunction "DIN_4") (pintype "passive"))
    )
    (net (code "39") (name "/ROW_3") (class "Default")
      (node (ref "D12") (pin "2") (pinfunction "DOUT_2") (pintype "passive"))
      (node (ref "D13") (pin "4") (pinfunction "DIN_4") (pintype "passive"))
    )
    (net (code "40") (name "/U0RXD") (class "Default")
      (node (ref "J4") (pin "2") (pinfunction "2_2") (pintype "passive"))
      (node (ref "U1") (pin "36") (pinfunction "U0RXD/GPIO44/CLK_OUT2_36") (pintype "passive"))
    )
    (net (code "41") (name "/U0TXD") (class "Default")
      (node (ref "J4") (pin "1") (pinfunction "1_1") (pintype "passive"))
      (node (ref "U1") (pin "37") (pinfunction "U0TXD/GPIO43/CLK_OUT1_37") (pintype "passive"))
    )
    (net (code "42") (name "/USB_N") (class "Default")
      (node (ref "D2") (pin "2") (pinfunction "2_2") (pintype "passive"))
      (node (ref "J1") (pin "A7") (pinfunction "DN1_A7") (pintype "passive"))
      (node (ref "J1") (pin "B7") (pinfunction "DN2_B7") (pintype "passive"))
      (node (ref "U1") (pin "13") (pinfunction "USB_D-/RTC_GPIO19/GPIO19/U1RTS/ADC2_CH8/CLK_OUT2_13") (pintype "passive"))
    )
    (net (code "43") (name "/USB_P") (class "Default")
      (node (ref "D3") (pin "2") (pinfunction "2_2") (pintype "passive"))
      (node (ref "J1") (pin "A6") (pinfunction "DP1_A6") (pintype "passive"))
      (node (ref "J1") (pin "B6") (pinfunction "DP2_B6") (pintype "passive"))
      (node (ref "U1") (pin "14") (pinfunction "USB_D+/RTC_GPIO20/GPIO20/U1CTS/ADC2_CH9/CLK_OUT1_14") (pintype "passive"))
    )
    (net (code "44") (name "GND") (class "Default")
      (node (ref "C1") (pin "1") (pinfunction "1_1") (pintype "passive"))
      (node (ref "C10") (pin "2") (pinfunction "2_2") (pintype "passive"))
      (node (ref "C11") (pin "2") (pinfunction "2_2") (pintype "passive"))
      (node (ref "C12") (pin "2") (pinfunction "2_2") (pintype "passive"))
      (node (ref "C14") (pin "1") (pinfunction "1_1") (pintype "passive"))
      (node (ref "C15") (pin "1") (pinfunction "1_1") (pintype "passive"))
      (node (ref "C16") (pin "1") (pinfunction "1_1") (pintype "passive"))
      (node (ref "C17") (pin "1") (pinfunction "1_1") (pintype "passive"))
      (node (ref "C18") (pin "1") (pinfunction "1_1") (pintype "passive"))
      (node (ref "C19") (pin "1") (pinfunction "1_1") (pintype "passive"))
      (node (ref "C2") (pin "1") (pinfunction "1_1") (pintype "passive"))
      (node (ref "C20") (pin "1") (pinfunction "1_1") (pintype "passive"))
      (node (ref "C21") (pin "1") (pinfunction "1_1") (pintype "passive"))
      (node (ref "C22") (pin "1") (pinfunction "1_1") (pintype "passive"))
      (node (ref "C23") (pin "1") (pinfunction "1_1") (pintype "passive"))
      (node (ref "C24") (pin "1") (pinfunction "1_1") (pintype "passive"))
      (node (ref "C25") (pin "1") (pinfunction "1_1") (pintype "passive"))
      (node (ref "C26") (pin "1") (pinfunction "1_1") (pintype "passive"))
      (node (ref "C28") (pin "1") (pinfunction "1_1") (pintype "passive"))
      (node (ref "C3") (pin "1") (pinfunction "1_1") (pintype "passive"))
      (node (ref "C4") (pin "1") (pinfunction "1_1") (pintype "passive"))
      (node (ref "C5") (pin "1") (pinfunction "1_1") (pintype "passive"))
      (node (ref "C6") (pin "2") (pinfunction "2_2") (pintype "passive"))
      (node (ref "C7") (pin "1") (pinfunction "1_1") (pintype "passive"))
      (node (ref "C8") (pin "2") (pinfunction "2_2") (pintype "passive"))
      (node (ref "C9") (pin "2") (pinfunction "2_2") (pintype "passive"))
      (node (ref "D1") (pin "1") (pinfunction "1_1") (pintype "passive"))
      (node (ref "D10") (pin "3") (pinfunction "VSS_3") (pintype "passive"))
      (node (ref "D11") (pin "3") (pinfunction "VSS_3") (pintype "passive"))
      (node (ref "D12") (pin "3") (pinfunction "VSS_3") (pintype "passive"))
      (node (ref "D13") (pin "3") (pinfunction "VSS_3") (pintype "passive"))
      (node (ref "D14") (pin "3") (pinfunction "VSS_3") (pintype "passive"))
      (node (ref "D15") (pin "3") (pinfunction "VSS_3") (pintype "passive"))
      (node (ref "D16") (pin "3") (pinfunction "VSS_3") (pintype "passive"))
      (node (ref "D2") (pin "1") (pinfunction "1_1") (pintype "passive"))
      (node (ref "D3") (pin "1") (pinfunction "1_1") (pintype "passive"))
      (node (ref "D4") (pin "2") (pinfunction "2_2") (pintype "passive"))
      (node (ref "D5") (pin "3") (pinfunction "VSS_3") (pintype "passive"))
      (node (ref "D6") (pin "3") (pinfunction "VSS_3") (pintype "passive"))
      (node (ref "D7") (pin "3") (pinfunction "VSS_3") (pintype "passive"))
      (node (ref "D8") (pin "3") (pinfunction "VSS_3") (pintype "passive"))
      (node (ref "D9") (pin "3") (pinfunction "VSS_3") (pintype "passive"))
      (node (ref "J1") (pin "A1B12") (pinfunction "GND_A1B12_A1B12") (pintype "passive"))
      (node (ref "J1") (pin "B1A12") (pinfunction "GND_B1A12_B1A12") (pintype "passive"))
      (node (ref "J1") (pin "S1") (pinfunction "SHIELD_1_S1") (pintype "passive"))
      (node (ref "J1") (pin "S2") (pinfunction "SHIELD_2_S2") (pintype "passive"))
      (node (ref "J1") (pin "S3") (pinfunction "SHIELD_3_S3") (pintype "passive"))
      (node (ref "J1") (pin "S4") (pinfunction "SHIELD_4_S4") (pintype "passive"))
      (node (ref "PD1") (pin "1") (pinfunction "1_1") (pintype "passive"))
      (node (ref "R1") (pin "1") (pinfunction "1_1") (pintype "passive"))
      (node (ref "R2") (pin "1") (pinfunction "1_1") (pintype "passive"))
      (node (ref "SW1") (pin "3") (pinfunction "3_3") (pintype "passive"))
      (node (ref "SW1") (pin "4") (pinfunction "4_4") (pintype "passive"))
      (node (ref "SW2") (pin "3") (pinfunction "3_3") (pintype "passive"))
      (node (ref "SW2") (pin "4") (pinfunction "4_4") (pintype "passive"))
      (node (ref "SW3") (pin "3") (pinfunction "3_3") (pintype "passive"))
      (node (ref "SW3") (pin "4") (pinfunction "4_4") (pintype "passive"))
      (node (ref "SW4") (pin "3") (pinfunction "3_3") (pintype "passive"))
      (node (ref "SW4") (pin "4") (pinfunction "4_4") (pintype "passive"))
      (node (ref "SW5") (pin "3") (pinfunction "3_3") (pintype "passive"))
      (node (ref "SW5") (pin "4") (pinfunction "4_4") (pintype "passive"))
      (node (ref "SW6") (pin "3") (pinfunction "3_3") (pintype "passive"))
      (node (ref "SW6") (pin "4") (pinfunction "4_4") (pintype "passive"))
      (node (ref "SW7") (pin "3") (pinfunction "3_3") (pintype "passive"))
      (node (ref "SW7") (pin "4") (pinfunction "4_4") (pintype "passive"))
      (node (ref "U1") (pin "1") (pinfunction "GND_1_1") (pintype "passive"))
      (node (ref "U1") (pin "40") (pinfunction "GND_40_40") (pintype "passive"))
      (node (ref "U1") (pin "41") (pinfunction "GND_EPAD_41") (pintype "passive"))
      (node (ref "U1") (pin "42") (pinfunction "GND_EPAD_42") (pintype "passive"))
      (node (ref "U1") (pin "43") (pinfunction "GND_EPAD_43") (pintype "passive"))
      (node (ref "U1") (pin "44") (pinfunction "GND_EPAD_44") (pintype "passive"))
      (node (ref "U1") (pin "45") (pinfunction "GND_EPAD_45") (pintype "passive"))
      (node (ref "U1") (pin "46") (pinfunction "GND_EPAD_46") (pintype "passive"))
      (node (ref "U1") (pin "47") (pinfunction "GND_EPAD_47") (pintype "passive"))
      (node (ref "U1") (pin "48") (pinfunction "GND_EPAD_48") (pintype "passive"))
      (node (ref "U1") (pin "49") (pinfunction "GND_EPAD_49") (pintype "passive"))
      (node (ref "U2") (pin "2") (pinfunction "GND_2") (pintype "power_in"))
      (node (ref "U2") (pin "4") (pinfunction "GND_4") (pintype "power_in"))
      (node (ref "U3") (pin "2") (pinfunction "V-_2") (pintype "passive"))
      (node (ref "U3") (pin "3") (pinfunction "IN+_3") (pintype "passive"))
      (node (ref "U4") (pin "1") (pinfunction "OE_1") (pintype "passive"))
      (node (ref "U4") (pin "3") (pinfunction "GND_3") (pintype "passive"))
    )
    (net (code "45") (name "Net-(D4-Pad1)") (class "Default")
      (node (ref "D4") (pin "1") (pinfunction "1_1") (pintype "passive"))
      (node (ref "R3") (pin "1") (pinfunction "1_1") (pintype "passive"))
    )
    (net (code "46") (name "Net-(D5-DOUT)") (class "Default")
      (node (ref "D5") (pin "2") (pinfunction "DOUT_2") (pintype "passive"))
      (node (ref "D6") (pin "4") (pinfunction "DIN_4") (pintype "passive"))
    )
    (net (code "47") (name "Net-(D6-DOUT)") (class "Default")
      (node (ref "D6") (pin "2") (pinfunction "DOUT_2") (pintype "passive"))
      (node (ref "D7") (pin "4") (pinfunction "DIN_4") (pintype "passive"))
    )
    (net (code "48") (name "Net-(D7-DOUT)") (class "Default")
      (node (ref "D7") (pin "2") (pinfunction "DOUT_2") (pintype "passive"))
      (node (ref "D8") (pin "4") (pinfunction "DIN_4") (pintype "passive"))
    )
    (net (code "49") (name "Net-(D10-DIN)") (class "Default")
      (node (ref "D10") (pin "4") (pinfunction "DIN_4") (pintype "passive"))
      (node (ref "D9") (pin "2") (pinfunction "DOUT_2") (pintype "passive"))
    )
    (net (code "50") (name "Net-(D10-DOUT)") (class "Default")
      (node (ref "D10") (pin "2") (pinfunction "DOUT_2") (pintype "passive"))
      (node (ref "D11") (pin "4") (pinfunction "DIN_4") (pintype "passive"))
    )
    (net (code "51") (name "Net-(D11-DOUT)") (class "Default")
      (node (ref "D11") (pin "2") (pinfunction "DOUT_2") (pintype "passive"))
      (node (ref "D12") (pin "4") (pinfunction "DIN_4") (pintype "passive"))
    )
    (net (code "52") (name "Net-(D13-DOUT)") (class "Default")
      (node (ref "D13") (pin "2") (pinfunction "DOUT_2") (pintype "passive"))
      (node (ref "D14") (pin "4") (pinfunction "DIN_4") (pintype "passive"))
    )
    (net (code "53") (name "Net-(D14-DOUT)") (class "Default")
      (node (ref "D14") (pin "2") (pinfunction "DOUT_2") (pintype "passive"))
      (node (ref "D15") (pin "4") (pinfunction "DIN_4") (pintype "passive"))
    )
    (net (code "54") (name "Net-(D15-DOUT)") (class "Default")
      (node (ref "D15") (pin "2") (pinfunction "DOUT_2") (pintype "passive"))
      (node (ref "D16") (pin "4") (pinfunction "DIN_4") (pintype "passive"))
    )
    (net (code "55") (name "Net-(J1-CC1)") (class "Default")
      (node (ref "J1") (pin "A5") (pinfunction "CC1_A5") (pintype "passive"))
      (node (ref "R2") (pin "2") (pinfunction "2_2") (pintype "passive"))
    )
    (net (code "56") (name "Net-(J1-CC2)") (class "Default")
      (node (ref "J1") (pin "B5") (pinfunction "CC2_B5") (pintype "passive"))
      (node (ref "R1") (pin "2") (pinfunction "2_2") (pintype "passive"))
    )
    (net (code "57") (name "Net-(U3-IN-)") (class "Default")
      (node (ref "C13") (pin "1") (pinfunction "1_1") (pintype "passive"))
      (node (ref "PD1") (pin "2") (pinfunction "2_2") (pintype "passive"))
      (node (ref "R10") (pin "1") (pinfunction "1_1") (pintype "passive"))
      (node (ref "U3") (pin "4") (pinfunction "IN-_4") (pintype "passive"))
    )
    (net (code "58") (name "unconnected-(D16-DOUT-Pad2)") (class "Default")
      (node (ref "D16") (pin "2") (pinfunction "DOUT_2") (pintype "passive+no_connect"))
    )
    (net (code "59") (name "unconnected-(J1-SBU1-PadA8)") (class "Default")
      (node (ref "J1") (pin "A8") (pinfunction "SBU1_A8") (pintype "passive+no_connect"))
    )
    (net (code "60") (name "unconnected-(J1-SBU2-PadB8)") (class "Default")
      (node (ref "J1") (pin "B8") (pinfunction "SBU2_B8") (pintype "passive+no_connect"))
    )
  )
)
